# Buck_Regulator.net
KiCad netlist of a schematic drawn in Altium Designer
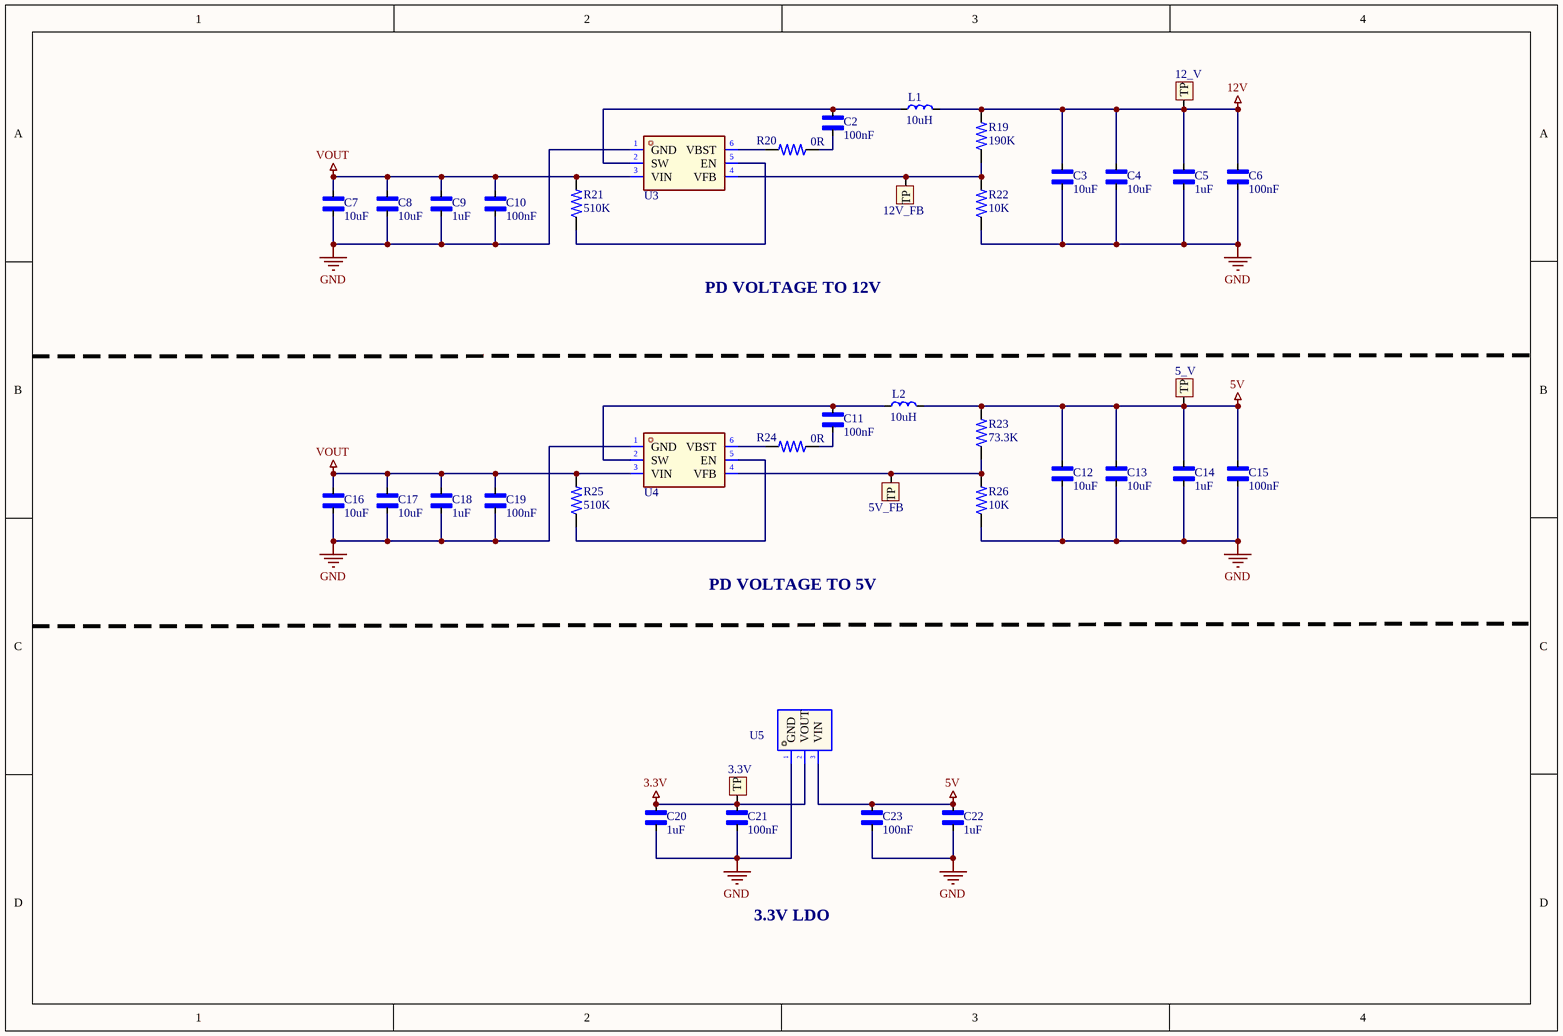
[diagram p0: Buck_Regulator.SchDoc]

(export (version "E")
  (design (tool "Eeschema 10.0.6"))
  (components
    (comp (ref "3.3V")
      (value "TEST POINT")
      (footprint "TESTPOINT")
      (libsource (lib "USB_PD_DVD") (part "TEST POINT"))
    )
    (comp (ref "5V_FB")
      (value "TEST POINT")
      (footprint "TESTPOINT")
      (libsource (lib "") (part "TEST POINT_1"))
    )
    (comp (ref "5_V")
      (value "TEST POINT")
      (footprint "TESTPOINT")
      (libsource (lib "USB_PD_DVD") (part "TEST POINT"))
    )
    (comp (ref "12V_FB")
      (value "TEST POINT")
      (footprint "TESTPOINT")
      (libsource (lib "") (part "TEST POINT_1"))
    )
    (comp (ref "12_V")
      (value "TEST POINT")
      (footprint "TESTPOINT")
      (libsource (lib "USB_PD_DVD") (part "TEST POINT"))
    )
    (comp (ref "C2")
      (value "100nF")
      (footprint "CAP 0402")
      (fields
        (field (name "VOLTAGE") "50V")
        (field (name "TOLERANCE") "±10%")
        (field (name "Comment") "SMD capacitor")
      )
      (libsource (lib "USB_PD_DVD") (part "CAP_SMD_CERAMIC"))
    )
    (comp (ref "C3")
      (value "10uF")
      (footprint "CAP_0805")
      (fields
        (field (name "VOLTAGE") "50V")
        (field (name "TOLERANCE") "±10%")
        (field (name "Comment") "SMD capacitor")
      )
      (libsource (lib "USB_PD_DVD") (part "CAP_SMD_CERAMIC"))
    )
    (comp (ref "C4")
      (value "10uF")
      (footprint "CAP_0805")
      (fields
        (field (name "VOLTAGE") "50V")
        (field (name "TOLERANCE") "±10%")
        (field (name "Comment") "SMD capacitor")
      )
      (libsource (lib "USB_PD_DVD") (part "CAP_SMD_CERAMIC"))
    )
    (comp (ref "C5")
      (value "1uF")
      (footprint "CAP 0402")
      (fields
        (field (name "VOLTAGE") "50V")
        (field (name "TOLERANCE") "±10%")
        (field (name "Comment") "SMD capacitor")
      )
      (libsource (lib "USB_PD_DVD") (part "CAP_SMD_CERAMIC"))
    )
    (comp (ref "C6")
      (value "100nF")
      (footprint "CAP 0402")
      (fields
        (field (name "VOLTAGE") "50V")
        (field (name "TOLERANCE") "±10%")
        (field (name "Comment") "SMD capacitor")
      )
      (libsource (lib "USB_PD_DVD") (part "CAP_SMD_CERAMIC"))
    )
    (comp (ref "C7")
      (value "10uF")
      (footprint "CAP_0805")
      (fields
        (field (name "VOLTAGE") "50V")
        (field (name "TOLERANCE") "±10%")
        (field (name "Comment") "SMD capacitor")
      )
      (libsource (lib "USB_PD_DVD") (part "CAP_SMD_CERAMIC"))
    )
    (comp (ref "C8")
      (value "10uF")
      (footprint "CAP_0805")
      (fields
        (field (name "VOLTAGE") "50V")
        (field (name "TOLERANCE") "±10%")
        (field (name "Comment") "SMD capacitor")
      )
      (libsource (lib "USB_PD_DVD") (part "CAP_SMD_CERAMIC"))
    )
    (comp (ref "C9")
      (value "1uF")
      (footprint "CAP 0402")
      (fields
        (field (name "VOLTAGE") "50V")
        (field (name "TOLERANCE") "±10%")
        (field (name "Comment") "SMD capacitor")
      )
      (libsource (lib "USB_PD_DVD") (part "CAP_SMD_CERAMIC"))
    )
    (comp (ref "C10")
      (value "100nF")
      (footprint "CAP 0402")
      (fields
        (field (name "VOLTAGE") "50V")
        (field (name "TOLERANCE") "±10%")
        (field (name "Comment") "SMD capacitor")
      )
      (libsource (lib "USB_PD_DVD") (part "CAP_SMD_CERAMIC"))
    )
    (comp (ref "C11")
      (value "100nF")
      (footprint "CAP 0402")
      (fields
        (field (name "VOLTAGE") "50V")
        (field (name "TOLERANCE") "±10%")
        (field (name "Comment") "SMD capacitor")
      )
      (libsource (lib "USB_PD_DVD") (part "CAP_SMD_CERAMIC"))
    )
    (comp (ref "C12")
      (value "10uF")
      (footprint "CAP_0805")
      (fields
        (field (name "VOLTAGE") "50V")
        (field (name "TOLERANCE") "±10%")
        (field (name "Comment") "SMD capacitor")
      )
      (libsource (lib "USB_PD_DVD") (part "CAP_SMD_CERAMIC"))
    )
    (comp (ref "C13")
      (value "10uF")
      (footprint "CAP_0805")
      (fields
        (field (name "VOLTAGE") "50V")
        (field (name "TOLERANCE") "±10%")
        (field (name "Comment") "SMD capacitor")
      )
      (libsource (lib "USB_PD_DVD") (part "CAP_SMD_CERAMIC"))
    )
    (comp (ref "C14")
      (value "1uF")
      (footprint "CAP 0402")
      (fields
        (field (name "VOLTAGE") "50V")
        (field (name "TOLERANCE") "±10%")
        (field (name "Comment") "SMD capacitor")
      )
      (libsource (lib "USB_PD_DVD") (part "CAP_SMD_CERAMIC"))
    )
    (comp (ref "C15")
      (value "100nF")
      (footprint "CAP 0402")
      (fields
        (field (name "VOLTAGE") "50V")
        (field (name "TOLERANCE") "±10%")
        (field (name "Comment") "SMD capacitor")
      )
      (libsource (lib "USB_PD_DVD") (part "CAP_SMD_CERAMIC"))
    )
    (comp (ref "C16")
      (value "10uF")
      (footprint "CAP_0805")
      (fields
        (field (name "VOLTAGE") "50V")
        (field (name "TOLERANCE") "±10%")
        (field (name "Comment") "SMD capacitor")
      )
      (libsource (lib "USB_PD_DVD") (part "CAP_SMD_CERAMIC"))
    )
    (comp (ref "C17")
      (value "10uF")
      (footprint "CAP_0805")
      (fields
        (field (name "VOLTAGE") "50V")
        (field (name "TOLERANCE") "±10%")
        (field (name "Comment") "SMD capacitor")
      )
      (libsource (lib "USB_PD_DVD") (part "CAP_SMD_CERAMIC"))
    )
    (comp (ref "C18")
      (value "1uF")
      (footprint "CAP 0402")
      (fields
        (field (name "VOLTAGE") "50V")
        (field (name "TOLERANCE") "±10%")
        (field (name "Comment") "SMD capacitor")
      )
      (libsource (lib "USB_PD_DVD") (part "CAP_SMD_CERAMIC"))
    )
    (comp (ref "C19")
      (value "100nF")
      (footprint "CAP 0402")
      (fields
        (field (name "VOLTAGE") "50V")
        (field (name "TOLERANCE") "±10%")
        (field (name "Comment") "SMD capacitor")
      )
      (libsource (lib "USB_PD_DVD") (part "CAP_SMD_CERAMIC"))
    )
    (comp (ref "C20")
      (value "1uF")
      (footprint "CAP 0402")
      (fields
        (field (name "VOLTAGE") "50V")
        (field (name "TOLERANCE") "±10%")
        (field (name "Comment") "SMD capacitor")
      )
      (libsource (lib "USB_PD_DVD") (part "CAP_SMD_CERAMIC"))
    )
    (comp (ref "C21")
      (value "100nF")
      (footprint "CAP 0402")
      (fields
        (field (name "VOLTAGE") "50V")
        (field (name "TOLERANCE") "±10%")
        (field (name "Comment") "SMD capacitor")
      )
      (libsource (lib "USB_PD_DVD") (part "CAP_SMD_CERAMIC"))
    )
    (comp (ref "C22")
      (value "1uF")
      (footprint "CAP 0402")
      (fields
        (field (name "VOLTAGE") "50V")
        (field (name "TOLERANCE") "±10%")
        (field (name "Comment") "SMD capacitor")
      )
      (libsource (lib "USB_PD_DVD") (part "CAP_SMD_CERAMIC"))
    )
    (comp (ref "C23")
      (value "100nF")
      (footprint "CAP 0402")
      (fields
        (field (name "VOLTAGE") "50V")
        (field (name "TOLERANCE") "±10%")
        (field (name "Comment") "SMD capacitor")
      )
      (libsource (lib "USB_PD_DVD") (part "CAP_SMD_CERAMIC"))
    )
    (comp (ref "L1")
      (value "10uH")
      (footprint "INDP7166X50N")
      (description "FIXED IND 10uH 4.5A 57mΩ SMD,6.6x7.1mm")
      (fields
        (field (name "MANIFACTURING PART NUMBER") "PSPMAA0605H-100M-ANP")
        (field (name "Comment") "POWER INDUCTOR")
      )
      (libsource (lib "USB_PD_DVD") (part "PSPMAA0605H-100M-ANP"))
    )
    (comp (ref "L2")
      (value "10uH")
      (footprint "INDP7166X50N")
      (description "FIXED IND 10uH 4.5A 57mΩ SMD,6.6x7.1mm")
      (fields
        (field (name "MANIFACTURING PART NUMBER") "PSPMAA0605H-100M-ANP")
        (field (name "Comment") "POWER INDUCTOR")
      )
      (libsource (lib "USB_PD_DVD") (part "PSPMAA0605H-100M-ANP"))
    )
    (comp (ref "R19")
      (value "190K")
      (footprint "RES 0402")
      (fields (field (name "TOLERANCE") "±5%") (field (name "Comment") "SMD resistor"))
      (libsource (lib "USB_PD_DVD") (part "RES_SMD_CERAMIC"))
    )
    (comp (ref "R20")
      (value "0R")
      (footprint "RES 0402")
      (fields (field (name "TOLERANCE") "±5%") (field (name "Comment") "SMD resistor"))
      (libsource (lib "USB_PD_DVD") (part "RES_SMD_CERAMIC"))
    )
    (comp (ref "R21")
      (value "510K")
      (footprint "RES 0402")
      (fields (field (name "TOLERANCE") "±5%") (field (name "Comment") "SMD resistor"))
      (libsource (lib "USB_PD_DVD") (part "RES_SMD_CERAMIC"))
    )
    (comp (ref "R22")
      (value "10K")
      (footprint "RES 0402")
      (fields (field (name "TOLERANCE") "±5%") (field (name "Comment") "SMD resistor"))
      (libsource (lib "USB_PD_DVD") (part "RES_SMD_CERAMIC"))
    )
    (comp (ref "R23")
      (value "73.3K")
      (footprint "RES 0402")
      (fields (field (name "TOLERANCE") "±5%") (field (name "Comment") "SMD resistor"))
      (libsource (lib "USB_PD_DVD") (part "RES_SMD_CERAMIC"))
    )
    (comp (ref "R24")
      (value "0R")
      (footprint "RES 0402")
      (fields (field (name "TOLERANCE") "±5%") (field (name "Comment") "SMD resistor"))
      (libsource (lib "USB_PD_DVD") (part "RES_SMD_CERAMIC"))
    )
    (comp (ref "R25")
      (value "510K")
      (footprint "RES 0402")
      (fields (field (name "TOLERANCE") "±5%") (field (name "Comment") "SMD resistor"))
      (libsource (lib "USB_PD_DVD") (part "RES_SMD_CERAMIC"))
    )
    (comp (ref "R26")
      (value "10K")
      (footprint "RES 0402")
      (fields (field (name "TOLERANCE") "±5%") (field (name "Comment") "SMD resistor"))
      (libsource (lib "USB_PD_DVD") (part "RES_SMD_CERAMIC"))
    )
    (comp (ref "U3")
      (value "Buck IC")
      (footprint "SOT-23-6_L2.9-W1.6-P0.95-LS2.8-BR")
      (description "Buck Adjustable 4.5V~36V 3A TSOT-23-6 DC-DC Converters ROHS")
      (fields
        (field (name "MANIFACTURING PART NUMBER") "TPP363080-T6TR")
        (field (name "JLCPCB PART #") "C18236275")
      )
      (libsource (lib "USB_PD_DVD") (part "TPP363080-T6TR"))
    )
    (comp (ref "U4")
      (value "Buck IC")
      (footprint "SOT-23-6_L2.9-W1.6-P0.95-LS2.8-BR")
      (description "Buck Adjustable 4.5V~36V 3A TSOT-23-6 DC-DC Converters ROHS")
      (fields
        (field (name "MANIFACTURING PART NUMBER") "TPP363080-T6TR")
        (field (name "JLCPCB PART #") "C18236275")
      )
      (libsource (lib "USB_PD_DVD") (part "TPP363080-T6TR"))
    )
    (comp (ref "U5")
      (value "3.3V LDO")
      (footprint "SOT-89-3_L4.5-W2.5-P1.50-LS4.1-BR")
      (fields
        (field (name "MANIFACTURING PART NUMBER") "AMS1117S-3.3")
        (field (name "JLCPCB PART #") "JSMSEMI")
      )
      (libsource (lib "USB_PD_DVD") (part "AMS1117S-3.3"))
    )
  )
  (nets
    (net (code "1") (name "3.3V") (class "Default")
      (node (ref "3.3V") (pin "1") (pinfunction "TP_1") (pintype "passive"))
      (node (ref "C20") (pin "1") (pinfunction "1_1") (pintype "passive"))
      (node (ref "C21") (pin "1") (pinfunction "1_1") (pintype "passive"))
      (node (ref "U5") (pin "2") (pinfunction "VOUT_2") (pintype "passive"))
    )
    (net (code "2") (name "5V") (class "Default")
      (node (ref "5_V") (pin "1") (pinfunction "TP_1") (pintype "passive"))
      (node (ref "C12") (pin "1") (pinfunction "1_1") (pintype "passive"))
      (node (ref "C13") (pin "1") (pinfunction "1_1") (pintype "passive"))
      (node (ref "C14") (pin "1") (pinfunction "1_1") (pintype "passive"))
      (node (ref "C15") (pin "1") (pinfunction "1_1") (pintype "passive"))
      (node (ref "C22") (pin "1") (pinfunction "1_1") (pintype "passive"))
      (node (ref "C23") (pin "1") (pinfunction "1_1") (pintype "passive"))
      (node (ref "L2") (pin "2") (pinfunction "2_2") (pintype "passive"))
      (node (ref "R23") (pin "2") (pinfunction "2_2") (pintype "passive"))
      (node (ref "U5") (pin "3") (pinfunction "VIN_3") (pintype "passive"))
    )
    (net (code "3") (name "12V") (class "Default")
      (node (ref "12_V") (pin "1") (pinfunction "TP_1") (pintype "passive"))
      (node (ref "C3") (pin "1") (pinfunction "1_1") (pintype "passive"))
      (node (ref "C4") (pin "1") (pinfunction "1_1") (pintype "passive"))
      (node (ref "C5") (pin "1") (pinfunction "1_1") (pintype "passive"))
      (node (ref "C6") (pin "1") (pinfunction "1_1") (pintype "passive"))
      (node (ref "L1") (pin "2") (pinfunction "2_2") (pintype "passive"))
      (node (ref "R19") (pin "2") (pinfunction "2_2") (pintype "passive"))
    )
    (net (code "4") (name "GND") (class "Default")
      (node (ref "C10") (pin "2") (pinfunction "2_2") (pintype "passive"))
      (node (ref "C12") (pin "2") (pinfunction "2_2") (pintype "passive"))
      (node (ref "C13") (pin "2") (pinfunction "2_2") (pintype "passive"))
      (node (ref "C14") (pin "2") (pinfunction "2_2") (pintype "passive"))
      (node (ref "C15") (pin "2") (pinfunction "2_2") (pintype "passive"))
      (node (ref "C16") (pin "2") (pinfunction "2_2") (pintype "passive"))
      (node (ref "C17") (pin "2") (pinfunction "2_2") (pintype "passive"))
      (node (ref "C18") (pin "2") (pinfunction "2_2") (pintype "passive"))
      (node (ref "C19") (pin "2") (pinfunction "2_2") (pintype "passive"))
      (node (ref "C20") (pin "2") (pinfunction "2_2") (pintype "passive"))
      (node (ref "C21") (pin "2") (pinfunction "2_2") (pintype "passive"))
      (node (ref "C22") (pin "2") (pinfunction "2_2") (pintype "passive"))
      (node (ref "C23") (pin "2") (pinfunction "2_2") (pintype "passive"))
      (node (ref "C3") (pin "2") (pinfunction "2_2") (pintype "passive"))
      (node (ref "C4") (pin "2") (pinfunction "2_2") (pintype "passive"))
      (node (ref "C5") (pin "2") (pinfunction "2_2") (pintype "passive"))
      (node (ref "C6") (pin "2") (pinfunction "2_2") (pintype "passive"))
      (node (ref "C7") (pin "2") (pinfunction "2_2") (pintype "passive"))
      (node (ref "C8") (pin "2") (pinfunction "2_2") (pintype "passive"))
      (node (ref "C9") (pin "2") (pinfunction "2_2") (pintype "passive"))
      (node (ref "R22") (pin "1") (pinfunction "1_1") (pintype "passive"))
      (node (ref "R26") (pin "1") (pinfunction "1_1") (pintype "passive"))
      (node (ref "U3") (pin "1") (pinfunction "GND_1") (pintype "passive"))
      (node (ref "U4") (pin "1") (pinfunction "GND_1") (pintype "passive"))
      (node (ref "U5") (pin "1") (pinfunction "GND_1") (pintype "passive"))
    )
    (net (code "5") (name "Net-(5V_FB-TP)") (class "Default")
      (node (ref "5V_FB") (pin "1") (pinfunction "TP_1") (pintype "passive"))
      (node (ref "R23") (pin "1") (pinfunction "1_1") (pintype "passive"))
      (node (ref "R26") (pin "2") (pinfunction "2_2") (pintype "passive"))
      (node (ref "U4") (pin "4") (pinfunction "VFB_4") (pintype "passive"))
    )
    (net (code "6") (name "Net-(12V_FB-TP)") (class "Default")
      (node (ref "12V_FB") (pin "1") (pinfunction "TP_1") (pintype "passive"))
      (node (ref "R19") (pin "1") (pinfunction "1_1") (pintype "passive"))
      (node (ref "R22") (pin "2") (pinfunction "2_2") (pintype "passive"))
      (node (ref "U3") (pin "4") (pinfunction "VFB_4") (pintype "passive"))
    )
    (net (code "7") (name "Net-(C2-Pad2)") (class "Default")
      (node (ref "C2") (pin "2") (pinfunction "2_2") (pintype "passive"))
      (node (ref "R20") (pin "1") (pinfunction "1_1") (pintype "passive"))
    )
    (net (code "8") (name "Net-(C11-Pad2)") (class "Default")
      (node (ref "C11") (pin "2") (pinfunction "2_2") (pintype "passive"))
      (node (ref "R24") (pin "1") (pinfunction "1_1") (pintype "passive"))
    )
    (net (code "9") (name "Net-(U3-EN)") (class "Default")
      (node (ref "R21") (pin "1") (pinfunction "1_1") (pintype "passive"))
      (node (ref "U3") (pin "5") (pinfunction "EN_5") (pintype "passive"))
    )
    (net (code "10") (name "Net-(U3-SW)") (class "Default")
      (node (ref "C2") (pin "1") (pinfunction "1_1") (pintype "passive"))
      (node (ref "L1") (pin "1") (pinfunction "1_1") (pintype "passive"))
      (node (ref "U3") (pin "2") (pinfunction "SW_2") (pintype "passive"))
    )
    (net (code "11") (name "Net-(U3-VBST)") (class "Default")
      (node (ref "R20") (pin "2") (pinfunction "2_2") (pintype "passive"))
      (node (ref "U3") (pin "6") (pinfunction "VBST_6") (pintype "passive"))
    )
    (net (code "12") (name "Net-(U4-EN)") (class "Default")
      (node (ref "R25") (pin "1") (pinfunction "1_1") (pintype "passive"))
      (node (ref "U4") (pin "5") (pinfunction "EN_5") (pintype "passive"))
    )
    (net (code "13") (name "Net-(U4-SW)") (class "Default")
      (node (ref "C11") (pin "1") (pinfunction "1_1") (pintype "passive"))
      (node (ref "L2") (pin "1") (pinfunction "1_1") (pintype "passive"))
      (node (ref "U4") (pin "2") (pinfunction "SW_2") (pintype "passive"))
    )
    (net (code "14") (name "Net-(U4-VBST)") (class "Default")
      (node (ref "R24") (pin "2") (pinfunction "2_2") (pintype "passive"))
      (node (ref "U4") (pin "6") (pinfunction "VBST_6") (pintype "passive"))
    )
    (net (code "15") (name "VOUT") (class "Default")
      (node (ref "C10") (pin "1") (pinfunction "1_1") (pintype "passive"))
      (node (ref "C16") (pin "1") (pinfunction "1_1") (pintype "passive"))
      (node (ref "C17") (pin "1") (pinfunction "1_1") (pintype "passive"))
      (node (ref "C18") (pin "1") (pinfunction "1_1") (pintype "passive"))
      (node (ref "C19") (pin "1") (pinfunction "1_1") (pintype "passive"))
      (node (ref "C7") (pin "1") (pinfunction "1_1") (pintype "passive"))
      (node (ref "C8") (pin "1") (pinfunction "1_1") (pintype "passive"))
      (node (ref "C9") (pin "1") (pinfunction "1_1") (pintype "passive"))
      (node (ref "R21") (pin "2") (pinfunction "2_2") (pintype "passive"))
      (node (ref "R25") (pin "2") (pinfunction "2_2") (pintype "passive"))
      (node (ref "U3") (pin "3") (pinfunction "VIN_3") (pintype "passive"))
      (node (ref "U4") (pin "3") (pinfunction "VIN_3") (pintype "passive"))
    )
  )
)
